# ESP32-DevKitC_EDA.net
KiCad netlist of a schematic drawn in EasyEDA Pro
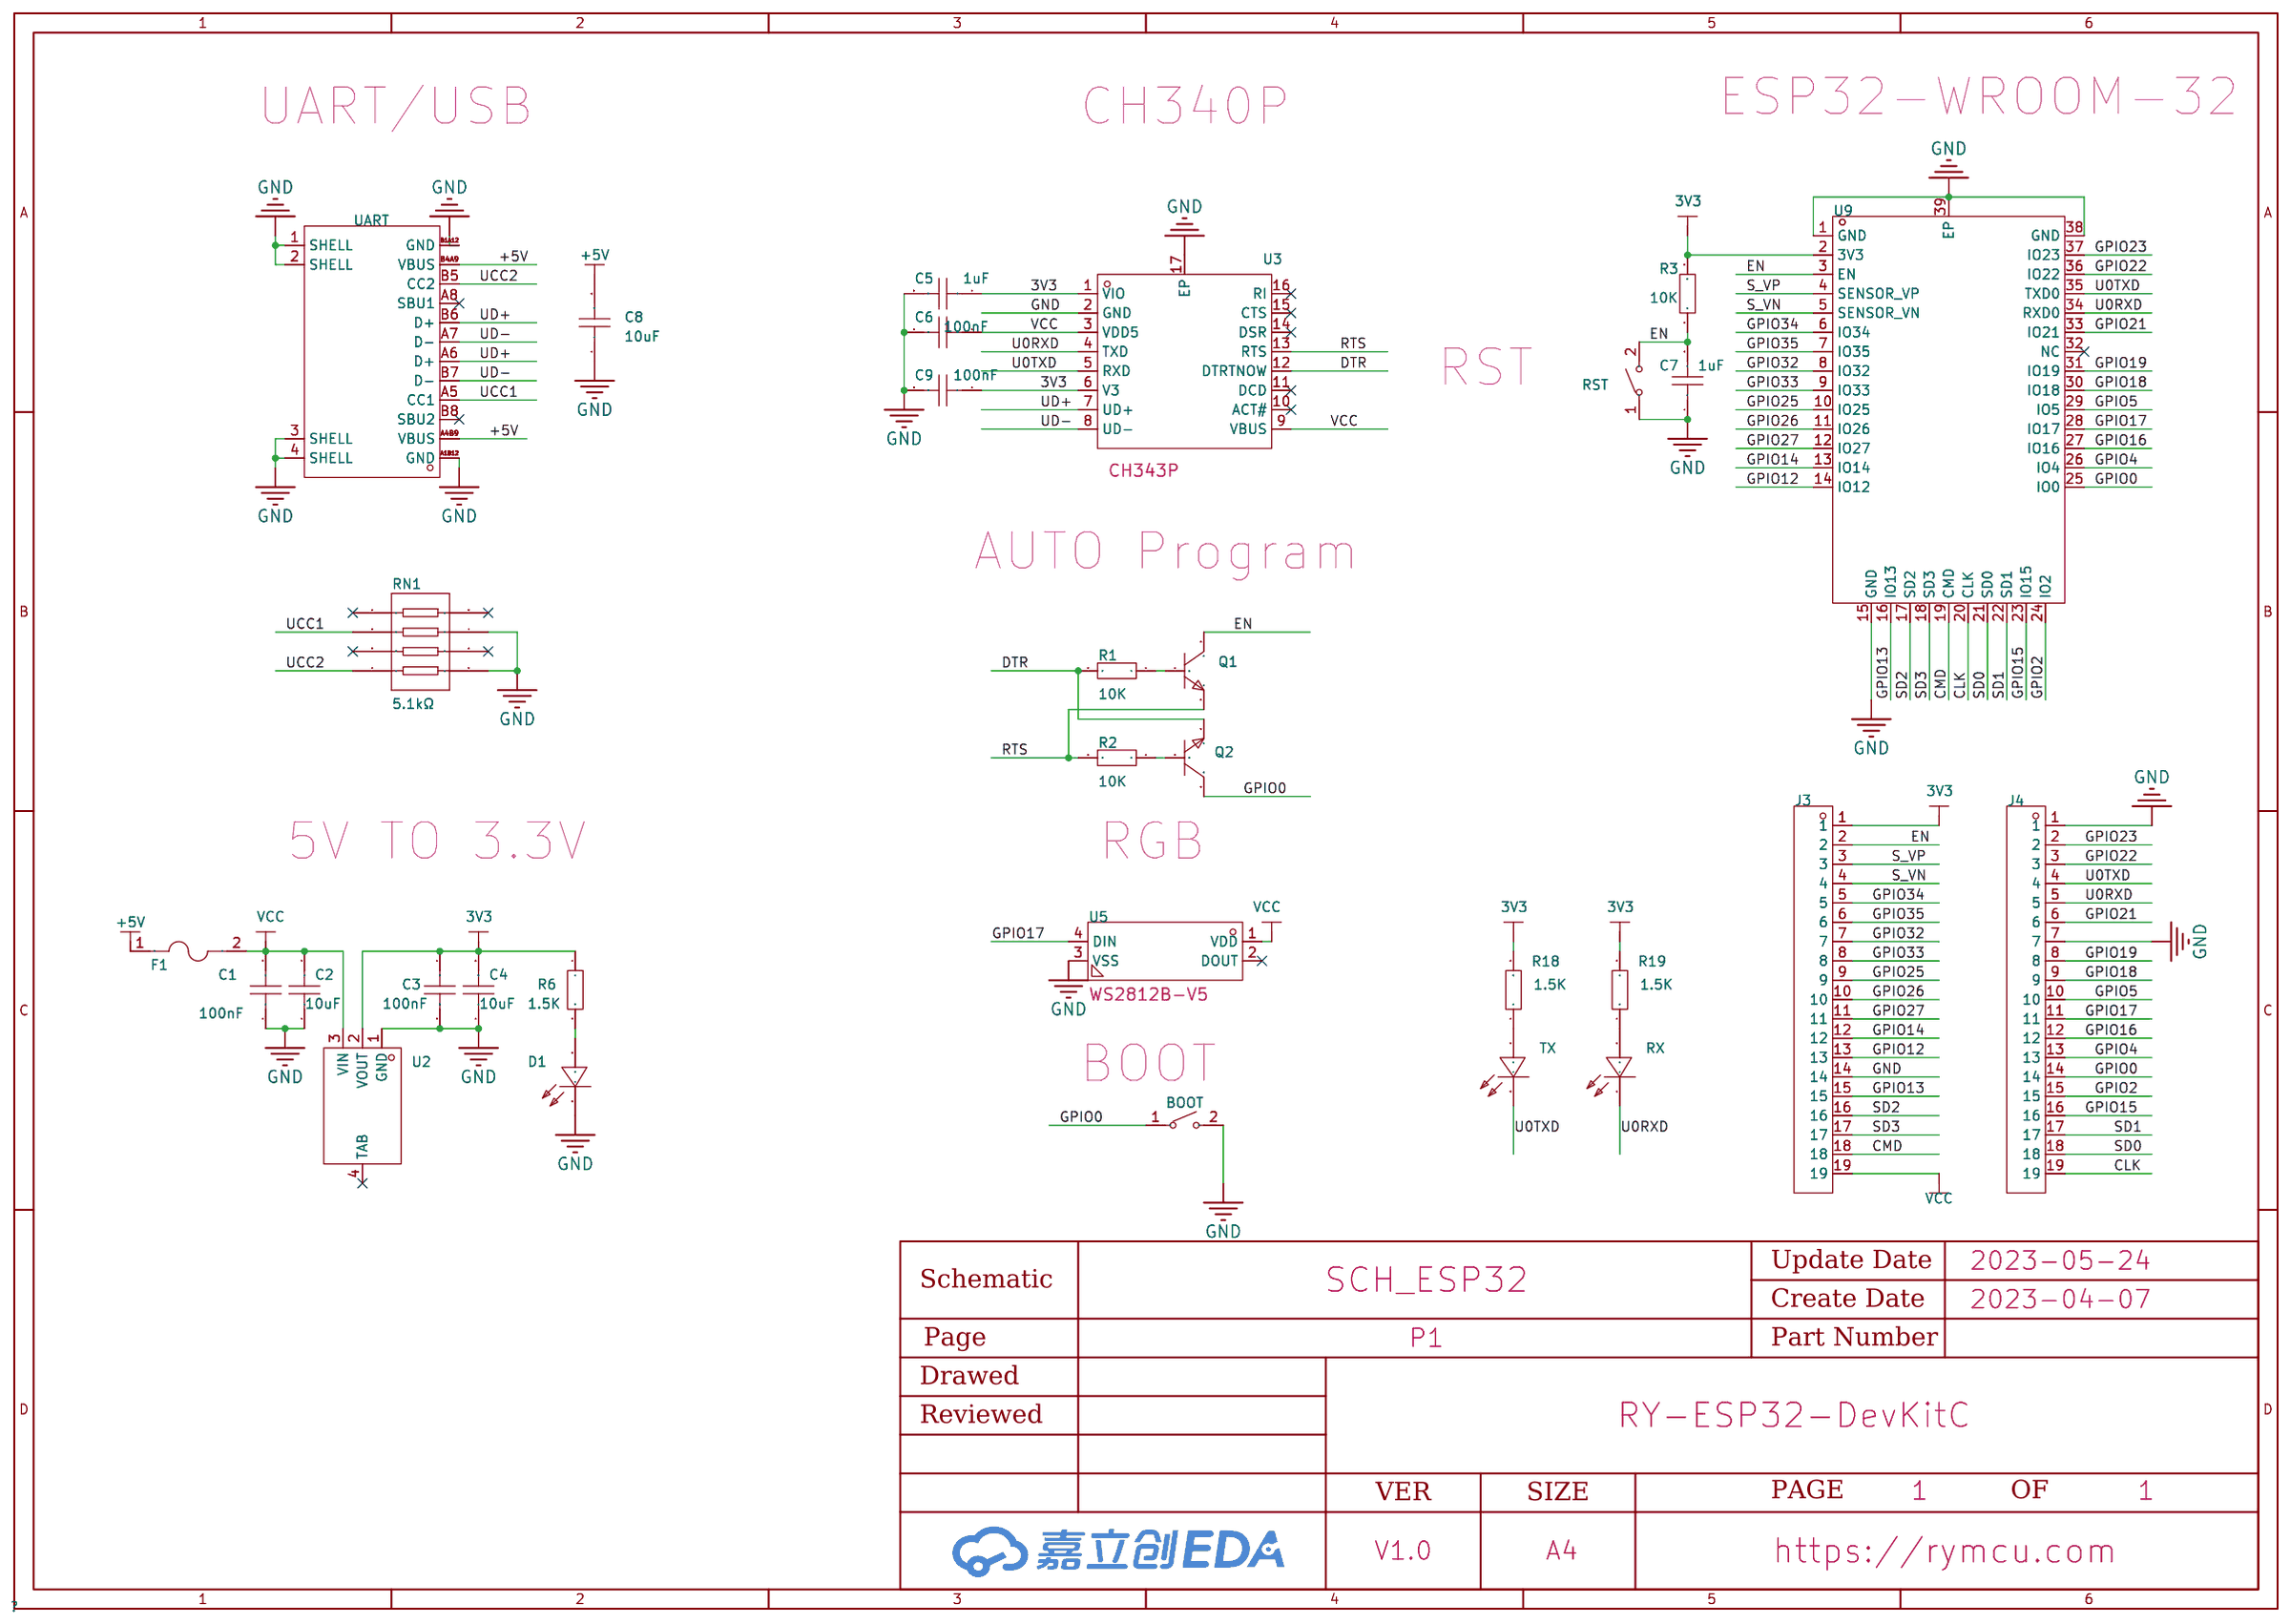
[diagram p0: schematic sheet]

(export (version "E")
  (design (tool "Eeschema 10.0.6"))
  (components
    (comp (ref "BOOT")
      (value "TS-1088R-02526")
      (footprint "easyedapro:SW-SMD_L3.9-W3.0-P4.45")
      (description "触点电流:50mA;额定电压(DC):12V;电路结构:单刀单掷;安装方式:立贴;按钮形状:圆形按钮;带灯:-;开关长度:3.9mm;开关宽度:2.93mm;开关高度:2.5mm;")
      (fields (field (name "Manufacturer") "XUNPU(讯普)"))
      (libsource (lib "easyedapro") (part "TS-1088R-02526"))
    )
    (comp (ref "C1")
      (value "100nF")
      (fields
        (field (name "Manufacturer Part") "CC0603KRX7R9BB104")
        (field (name "Manufacturer") "YAGEO(国巨)")
      )
      (libsource (lib "easyedapro") (part "CC0603KRX7R9BB104"))
    )
    (comp (ref "C2")
      (value "10uF")
      (fields
        (field (name "Manufacturer Part") "CC0805FRNPO9BN330")
        (field (name "Manufacturer") "YAGEO(国巨)")
      )
      (libsource (lib "easyedapro") (part "CC0805FRNPO9BN330"))
    )
    (comp (ref "C3")
      (value "100nF")
      (fields
        (field (name "Manufacturer Part") "CC0603KRX7R9BB104")
        (field (name "Manufacturer") "YAGEO(国巨)")
      )
      (libsource (lib "easyedapro") (part "CC0603KRX7R9BB104"))
    )
    (comp (ref "C4")
      (value "10uF")
      (fields
        (field (name "Manufacturer Part") "CC0805FRNPO9BN330")
        (field (name "Manufacturer") "YAGEO(国巨)")
      )
      (libsource (lib "easyedapro") (part "CC0805FRNPO9BN330"))
    )
    (comp (ref "C5")
      (value "1uF")
      (fields
        (field (name "Manufacturer Part") "CC0603KRX7R9BB104")
        (field (name "Manufacturer") "YAGEO(国巨)")
      )
      (libsource (lib "easyedapro") (part "CC0603KRX7R9BB104"))
    )
    (comp (ref "C6")
      (value "100nF")
      (fields
        (field (name "Manufacturer Part") "CC0603KRX7R9BB104")
        (field (name "Manufacturer") "YAGEO(国巨)")
      )
      (libsource (lib "easyedapro") (part "CC0603KRX7R9BB104"))
    )
    (comp (ref "C7")
      (value "1uF")
      (fields
        (field (name "Manufacturer Part") "CC0603KRX7R9BB104")
        (field (name "Manufacturer") "YAGEO(国巨)")
      )
      (libsource (lib "easyedapro") (part "CC0603KRX7R9BB104"))
    )
    (comp (ref "C8")
      (value "10uF")
      (fields
        (field (name "Manufacturer Part") "CC0805FRNPO9BN330")
        (field (name "Manufacturer") "YAGEO(国巨)")
      )
      (libsource (lib "easyedapro") (part "CC0805FRNPO9BN330"))
    )
    (comp (ref "C9")
      (value "100nF")
      (fields
        (field (name "Manufacturer Part") "CC0603KRX7R9BB104")
        (field (name "Manufacturer") "YAGEO(国巨)")
      )
      (libsource (lib "easyedapro") (part "CC0603KRX7R9BB104"))
    )
    (comp (ref "D1")
      (value "NCD0603R3")
      (fields (field (name "Manufacturer") "国星光电"))
      (libsource (lib "easyedapro") (part "NCD0603R3"))
    )
    (comp (ref "F1")
      (value "~")
      (footprint "easyedapro:F0805")
      (fields (field (name "Manufacturer Part") "ASMD0805-075") (field (name "Manufacturer") "JDTfuse集电通"))
      (libsource (lib "easyedapro") (part "ASMD0805-075"))
    )
    (comp (ref "J3")
      (value "2.54-1*19P反弯针")
      (footprint "easyedapro:HDR-TH_19P-P2.54-H-M-W10.5")
      (fields (field (name "Manufacturer") "BOOMELE(博穆精密)"))
      (libsource (lib "easyedapro") (part "DIP19"))
    )
    (comp (ref "J4")
      (value "2.54-1*19P反弯针")
      (footprint "easyedapro:HDR-TH_19P-P2.54-H-M-W10.5")
      (fields (field (name "Manufacturer") "BOOMELE(博穆精密)"))
      (libsource (lib "easyedapro") (part "DIP19"))
    )
    (comp (ref "Q1")
      (value "L8050QLT1G")
      (footprint "easyedapro:SOT-23-3_L2.9-W1.3-P1.90-LS2.4-BR")
      (description "集电极电流(Ic):800mA;集射极击穿电压(Vceo):25V;功率(Pd):225mW;晶体管类型:NPN;")
      (fields (field (name "Manufacturer") "LRC(乐山无线电)"))
      (libsource (lib "easyedapro") (part "L8050QLT1G"))
    )
    (comp (ref "Q2")
      (value "L8050QLT1G")
      (footprint "easyedapro:SOT-23-3_L2.9-W1.3-P1.90-LS2.4-BR")
      (description "集电极电流(Ic):800mA;集射极击穿电压(Vceo):25V;功率(Pd):225mW;晶体管类型:NPN;")
      (fields (field (name "Manufacturer") "LRC(乐山无线电)"))
      (libsource (lib "easyedapro") (part "L8050QLT1G"))
    )
    (comp (ref "R1")
      (value "10K")
      (footprint "easyedapro:R0603")
      (description "电阻类型:薄膜电阻;阻值:10kΩ;精度:±0.1%;功率:100mW;温度系数:±25ppm/;最大工作电压:75V;工作温度范围:-55~+155;")
      (fields
        (field (name "Manufacturer Part") "TR0603B10K0P0525Z")
        (field (name "Manufacturer") "EVER OHMS(天二科技)")
      )
      (libsource (lib "easyedapro") (part "TR0603B10KP05250.1W"))
    )
    (comp (ref "R2")
      (value "10K")
      (footprint "easyedapro:R0603")
      (description "电阻类型:薄膜电阻;阻值:10kΩ;精度:±0.1%;功率:100mW;温度系数:±25ppm/;最大工作电压:75V;工作温度范围:-55~+155;")
      (fields
        (field (name "Manufacturer Part") "TR0603B10K0P0525Z")
        (field (name "Manufacturer") "EVER OHMS(天二科技)")
      )
      (libsource (lib "easyedapro") (part "TR0603B10KP05250.1W"))
    )
    (comp (ref "R3")
      (value "10K")
      (footprint "easyedapro:R0603")
      (description "电阻类型:薄膜电阻;阻值:10kΩ;精度:±0.1%;功率:100mW;温度系数:±25ppm/;最大工作电压:75V;工作温度范围:-55~+155;")
      (fields
        (field (name "Manufacturer Part") "TR0603B10K0P0525Z")
        (field (name "Manufacturer") "EVER OHMS(天二科技)")
      )
      (libsource (lib "easyedapro") (part "TR0603B10KP05250.1W"))
    )
    (comp (ref "R6")
      (value "1.5K")
      (footprint "easyedapro:R0603")
      (description "电阻类型:薄膜电阻;阻值:10kΩ;精度:±0.1%;功率:100mW;温度系数:±25ppm/;最大工作电压:75V;工作温度范围:-55~+155;")
      (fields
        (field (name "Manufacturer Part") "TR0603B10K0P0525Z")
        (field (name "Manufacturer") "EVER OHMS(天二科技)")
      )
      (libsource (lib "easyedapro") (part "TR0603B10KP05250.1W"))
    )
    (comp (ref "R18")
      (value "1.5K")
      (footprint "easyedapro:R0603")
      (description "电阻类型:薄膜电阻;阻值:10kΩ;精度:±0.1%;功率:100mW;温度系数:±25ppm/;最大工作电压:75V;工作温度范围:-55~+155;")
      (fields
        (field (name "Manufacturer Part") "TR0603B10K0P0525Z")
        (field (name "Manufacturer") "EVER OHMS(天二科技)")
      )
      (libsource (lib "easyedapro") (part "TR0603B10KP05250.1W"))
    )
    (comp (ref "R19")
      (value "1.5K")
      (footprint "easyedapro:R0603")
      (description "电阻类型:薄膜电阻;阻值:10kΩ;精度:±0.1%;功率:100mW;温度系数:±25ppm/;最大工作电压:75V;工作温度范围:-55~+155;")
      (fields
        (field (name "Manufacturer Part") "TR0603B10K0P0525Z")
        (field (name "Manufacturer") "EVER OHMS(天二科技)")
      )
      (libsource (lib "easyedapro") (part "TR0603B10KP05250.1W"))
    )
    (comp (ref "RN1")
      (value "5.1kΩ")
      (footprint "easyedapro:RES-ARRAY-SMD_0603-8P-L3.2-W1.6-BL")
      (description "阻值:5.1kΩ;精度:±5%;单个元件功率:62.5mW;温度系数:±200ppm/;电阻器数:4;引脚数:8;")
      (fields
        (field (name "Manufacturer Part") "4D03WGJ0512T5E")
        (field (name "Manufacturer") "UNI-ROYAL(厚声)")
      )
      (libsource (lib "easyedapro") (part "4D03WGJ0512T5E"))
    )
    (comp (ref "RST")
      (value "TS-1088R-02526")
      (footprint "easyedapro:SW-SMD_L3.9-W3.0-P4.45")
      (description "触点电流:50mA;额定电压(DC):12V;电路结构:单刀单掷;安装方式:立贴;按钮形状:圆形按钮;带灯:-;开关长度:3.9mm;开关宽度:2.93mm;开关高度:2.5mm;")
      (fields (field (name "Manufacturer") "XUNPU(讯普)"))
      (libsource (lib "easyedapro") (part "TS-1088R-02526"))
    )
    (comp (ref "RX")
      (value "NCD0603R3")
      (footprint "easyedapro:LED0603-R-RD_RED")
      (description "尺寸1.6x0.8x0.8；IF=20ma：1.6~2.6v，620~640nm,51~150mcd金线，光强高，功耗低，可靠性好，寿命长")
      (fields (field (name "Manufacturer") "国星光电"))
      (libsource (lib "easyedapro") (part "NCD0603R3"))
    )
    (comp (ref "TX")
      (value "NCD0603R3")
      (fields (field (name "Manufacturer") "国星光电"))
      (libsource (lib "easyedapro") (part "NCD0603R3"))
    )
    (comp (ref "U2")
      (value "~")
      (footprint "easyedapro:SOT-223-3_L6.5-W3.4-P2.30-LS7.0-BR")
      (description "输出类型:固定;输出极性:正;输出通道数:1;最大输入电压:18V;输出电压:3.3V;压差:1.4V@(1A);输出电流:800mA;电源纹波抑制比(PRSS):-;")
      (fields (field (name "Manufacturer Part") "AMS1117-3.3") (field (name "Manufacturer") "PUOLOP(迪浦)"))
      (libsource (lib "easyedapro") (part "AMS1117-3.3_C351784"))
    )
    (comp (ref "U3")
      (value "CH343P")
      (footprint "easyedapro:TQFN-16_L3.0-W3.0-P0.50-BL-EP1.7")
      (description "类型:-;协议类别:-;驱动器/接收器数:-;数据速率:-;")
      (fields (field (name "Manufacturer") "WCH(南京沁恒)") (field (name "LCSC Part Name") "CH343P"))
      (libsource (lib "easyedapro") (part "CH343P"))
    )
    (comp (ref "U5")
      (value "WS2812B-V5")
      (footprint "easyedapro:LED-SMD_4P-L5.0-W5.0-TL_WS2812B-B")
      (fields (field (name "LCSC Part Name") "WS2812B-V5"))
      (libsource (lib "easyedapro") (part "WS2812B-V5"))
    )
    (comp (ref "U9")
      (value "ESP32-WROOM-32")
      (footprint "easyedapro:WIFIM-SMD_ESP-WROOM-32")
      (description "WiFi+双模蓝牙 双核CPU 网口 顶配MCU 低功耗蓝牙 ESP32系列ESP-WROOM-32模组/ESP-32S 4MB")
      (fields (field (name "Manufacturer") "ESPRESSIF(乐鑫)"))
      (libsource (lib "easyedapro") (part "ESP-WROOM-32"))
    )
    (comp (ref "UART")
      (value "~")
      (footprint "easyedapro:USB-C-SMD_G-SWITCH_GT-USB-7010EN")
      (description "连接器类型:Type-C;公母:母座;触点数量:16;端口数量:1;安装方式:卧贴;")
      (fields
        (field (name "Manufacturer Part") "HC-TYPE-C-16P-01A-R")
        (field (name "Manufacturer") "HCTL(华灿天禄)")
      )
      (libsource (lib "easyedapro") (part "HC-TYPE-C-16P-01A-R"))
    )
  )
  (nets
    (net (code "1") (name "+5V") (class "Default")
      (node (ref "C8") (pin "2") (pinfunction "2_2") (pintype "input"))
      (node (ref "F1") (pin "1") (pinfunction "1_1") (pintype "input"))
      (node (ref "UART") (pin "A4B9") (pinfunction "VBUS_A4B9") (pintype "input"))
      (node (ref "UART") (pin "B4A9") (pinfunction "VBUS_B4A9") (pintype "input"))
    )
    (net (code "2") (name "/CLK") (class "Default")
      (node (ref "J4") (pin "19") (pinfunction "19_19") (pintype "input"))
      (node (ref "U9") (pin "20") (pinfunction "CLK_20") (pintype "input"))
    )
    (net (code "3") (name "/CMD") (class "Default")
      (node (ref "J3") (pin "18") (pinfunction "18_18") (pintype "input"))
      (node (ref "U9") (pin "19") (pinfunction "CMD_19") (pintype "input"))
    )
    (net (code "4") (name "/DTR") (class "Default")
      (node (ref "Q2") (pin "2") (pinfunction "E_2") (pintype "input"))
      (node (ref "R1") (pin "2") (pinfunction "2_2") (pintype "input"))
      (node (ref "U3") (pin "12") (pinfunction "DTRTNOW_12") (pintype "input"))
    )
    (net (code "5") (name "/EN") (class "Default")
      (node (ref "C7") (pin "2") (pinfunction "2_2") (pintype "input"))
      (node (ref "J3") (pin "2") (pinfunction "2_2") (pintype "input"))
      (node (ref "Q1") (pin "3") (pinfunction "C_3") (pintype "input"))
      (node (ref "R3") (pin "1") (pinfunction "1_1") (pintype "input"))
      (node (ref "RST") (pin "2") (pinfunction "2_2") (pintype "input"))
      (node (ref "U9") (pin "3") (pinfunction "EN_3") (pintype "input"))
    )
    (net (code "6") (name "/GPIO0") (class "Default")
      (node (ref "BOOT") (pin "1") (pinfunction "1_1") (pintype "input"))
      (node (ref "J4") (pin "14") (pinfunction "14_14") (pintype "input"))
      (node (ref "Q2") (pin "3") (pinfunction "C_3") (pintype "input"))
      (node (ref "U9") (pin "25") (pinfunction "IO0_25") (pintype "input"))
    )
    (net (code "7") (name "/GPIO2") (class "Default")
      (node (ref "J4") (pin "15") (pinfunction "15_15") (pintype "input"))
      (node (ref "U9") (pin "24") (pinfunction "IO2_24") (pintype "input"))
    )
    (net (code "8") (name "/GPIO4") (class "Default")
      (node (ref "J4") (pin "13") (pinfunction "13_13") (pintype "input"))
      (node (ref "U9") (pin "26") (pinfunction "IO4_26") (pintype "input"))
    )
    (net (code "9") (name "/GPIO5") (class "Default")
      (node (ref "J4") (pin "10") (pinfunction "10_10") (pintype "input"))
      (node (ref "U9") (pin "29") (pinfunction "IO5_29") (pintype "input"))
    )
    (net (code "10") (name "/GPIO12") (class "Default")
      (node (ref "J3") (pin "13") (pinfunction "13_13") (pintype "input"))
      (node (ref "U9") (pin "14") (pinfunction "IO12_14") (pintype "input"))
    )
    (net (code "11") (name "/GPIO13") (class "Default")
      (node (ref "J3") (pin "15") (pinfunction "15_15") (pintype "input"))
      (node (ref "U9") (pin "16") (pinfunction "IO13_16") (pintype "input"))
    )
    (net (code "12") (name "/GPIO14") (class "Default")
      (node (ref "J3") (pin "12") (pinfunction "12_12") (pintype "input"))
      (node (ref "U9") (pin "13") (pinfunction "IO14_13") (pintype "input"))
    )
    (net (code "13") (name "/GPIO15") (class "Default")
      (node (ref "J4") (pin "16") (pinfunction "16_16") (pintype "input"))
      (node (ref "U9") (pin "23") (pinfunction "IO15_23") (pintype "input"))
    )
    (net (code "14") (name "/GPIO16") (class "Default")
      (node (ref "J4") (pin "12") (pinfunction "12_12") (pintype "input"))
      (node (ref "U9") (pin "27") (pinfunction "IO16_27") (pintype "input"))
    )
    (net (code "15") (name "/GPIO17") (class "Default")
      (node (ref "J4") (pin "11") (pinfunction "11_11") (pintype "input"))
      (node (ref "U5") (pin "4") (pinfunction "DIN_4") (pintype "input"))
      (node (ref "U9") (pin "28") (pinfunction "IO17_28") (pintype "input"))
    )
    (net (code "16") (name "/GPIO18") (class "Default")
      (node (ref "J4") (pin "9") (pinfunction "9_9") (pintype "input"))
      (node (ref "U9") (pin "30") (pinfunction "IO18_30") (pintype "input"))
    )
    (net (code "17") (name "/GPIO19") (class "Default")
      (node (ref "J4") (pin "8") (pinfunction "8_8") (pintype "input"))
      (node (ref "U9") (pin "31") (pinfunction "IO19_31") (pintype "input"))
    )
    (net (code "18") (name "/GPIO21") (class "Default")
      (node (ref "J4") (pin "6") (pinfunction "6_6") (pintype "input"))
      (node (ref "U9") (pin "33") (pinfunction "IO21_33") (pintype "input"))
    )
    (net (code "19") (name "/GPIO22") (class "Default")
      (node (ref "J4") (pin "3") (pinfunction "3_3") (pintype "input"))
      (node (ref "U9") (pin "36") (pinfunction "IO22_36") (pintype "input"))
    )
    (net (code "20") (name "/GPIO23") (class "Default")
      (node (ref "J4") (pin "2") (pinfunction "2_2") (pintype "input"))
      (node (ref "U9") (pin "37") (pinfunction "IO23_37") (pintype "input"))
    )
    (net (code "21") (name "/GPIO25") (class "Default")
      (node (ref "J3") (pin "9") (pinfunction "9_9") (pintype "input"))
      (node (ref "U9") (pin "10") (pinfunction "IO25_10") (pintype "input"))
    )
    (net (code "22") (name "/GPIO26") (class "Default")
      (node (ref "J3") (pin "10") (pinfunction "10_10") (pintype "input"))
      (node (ref "U9") (pin "11") (pinfunction "IO26_11") (pintype "input"))
    )
    (net (code "23") (name "/GPIO27") (class "Default")
      (node (ref "J3") (pin "11") (pinfunction "11_11") (pintype "input"))
      (node (ref "U9") (pin "12") (pinfunction "IO27_12") (pintype "input"))
    )
    (net (code "24") (name "/GPIO32") (class "Default")
      (node (ref "J3") (pin "7") (pinfunction "7_7") (pintype "input"))
      (node (ref "U9") (pin "8") (pinfunction "IO32_8") (pintype "input"))
    )
    (net (code "25") (name "/GPIO33") (class "Default")
      (node (ref "J3") (pin "8") (pinfunction "8_8") (pintype "input"))
      (node (ref "U9") (pin "9") (pinfunction "IO33_9") (pintype "input"))
    )
    (net (code "26") (name "/GPIO34") (class "Default")
      (node (ref "J3") (pin "5") (pinfunction "5_5") (pintype "input"))
      (node (ref "U9") (pin "6") (pinfunction "IO34_6") (pintype "input"))
    )
    (net (code "27") (name "/GPIO35") (class "Default")
      (node (ref "J3") (pin "6") (pinfunction "6_6") (pintype "input"))
      (node (ref "U9") (pin "7") (pinfunction "IO35_7") (pintype "input"))
    )
    (net (code "28") (name "/RTS") (class "Default")
      (node (ref "Q1") (pin "2") (pinfunction "E_2") (pintype "input"))
      (node (ref "R2") (pin "2") (pinfunction "2_2") (pintype "input"))
      (node (ref "U3") (pin "13") (pinfunction "RTS_13") (pintype "input"))
    )
    (net (code "29") (name "/SD0") (class "Default")
      (node (ref "J4") (pin "18") (pinfunction "18_18") (pintype "input"))
      (node (ref "U9") (pin "21") (pinfunction "SD0_21") (pintype "input"))
    )
    (net (code "30") (name "/SD1") (class "Default")
      (node (ref "J4") (pin "17") (pinfunction "17_17") (pintype "input"))
      (node (ref "U9") (pin "22") (pinfunction "SD1_22") (pintype "input"))
    )
    (net (code "31") (name "/SD2") (class "Default")
      (node (ref "J3") (pin "16") (pinfunction "16_16") (pintype "input"))
      (node (ref "U9") (pin "17") (pinfunction "SD2_17") (pintype "input"))
    )
    (net (code "32") (name "/SD3") (class "Default")
      (node (ref "J3") (pin "17") (pinfunction "17_17") (pintype "input"))
      (node (ref "U9") (pin "18") (pinfunction "SD3_18") (pintype "input"))
    )
    (net (code "33") (name "/S_VN") (class "Default")
      (node (ref "J3") (pin "4") (pinfunction "4_4") (pintype "input"))
      (node (ref "U9") (pin "5") (pinfunction "SENSOR_VN_5") (pintype "input"))
    )
    (net (code "34") (name "/S_VP") (class "Default")
      (node (ref "J3") (pin "3") (pinfunction "3_3") (pintype "input"))
      (node (ref "U9") (pin "4") (pinfunction "SENSOR_VP_4") (pintype "input"))
    )
    (net (code "35") (name "/U0RXD") (class "Default")
      (node (ref "J4") (pin "5") (pinfunction "5_5") (pintype "input"))
      (node (ref "RX") (pin "2") (pinfunction "K_2") (pintype "input"))
      (node (ref "U3") (pin "4") (pinfunction "TXD_4") (pintype "input"))
      (node (ref "U9") (pin "34") (pinfunction "RXD0_34") (pintype "input"))
    )
    (net (code "36") (name "/U0TXD") (class "Default")
      (node (ref "J4") (pin "4") (pinfunction "4_4") (pintype "input"))
      (node (ref "TX") (pin "2") (pinfunction "K_2") (pintype "input"))
      (node (ref "U3") (pin "5") (pinfunction "RXD_5") (pintype "input"))
      (node (ref "U9") (pin "35") (pinfunction "TXD0_35") (pintype "input"))
    )
    (net (code "37") (name "/UCC1") (class "Default")
      (node (ref "RN1") (pin "2") (pinfunction "2_2") (pintype "input"))
      (node (ref "UART") (pin "A5") (pinfunction "CC1_A5") (pintype "input"))
    )
    (net (code "38") (name "/UCC2") (class "Default")
      (node (ref "RN1") (pin "4") (pinfunction "4_4") (pintype "input"))
      (node (ref "UART") (pin "B5") (pinfunction "CC2_B5") (pintype "input"))
    )
    (net (code "39") (name "/UD+") (class "Default")
      (node (ref "U3") (pin "7") (pinfunction "UD+_7") (pintype "input"))
      (node (ref "UART") (pin "A6") (pinfunction "D+_A6") (pintype "input"))
      (node (ref "UART") (pin "B6") (pinfunction "D+_B6") (pintype "input"))
    )
    (net (code "40") (name "/UD-") (class "Default")
      (node (ref "U3") (pin "8") (pinfunction "UD-_8") (pintype "input"))
      (node (ref "UART") (pin "A7") (pinfunction "D-_A7") (pintype "input"))
      (node (ref "UART") (pin "B7") (pinfunction "D-_B7") (pintype "input"))
    )
    (net (code "41") (name "3V3") (class "Default")
      (node (ref "C3") (pin "1") (pinfunction "1_1") (pintype "input"))
      (node (ref "C4") (pin "2") (pinfunction "2_2") (pintype "input"))
      (node (ref "C5") (pin "1") (pinfunction "1_1") (pintype "input"))
      (node (ref "C9") (pin "1") (pinfunction "1_1") (pintype "input"))
      (node (ref "J3") (pin "1") (pinfunction "1_1") (pintype "input"))
      (node (ref "R18") (pin "2") (pinfunction "2_2") (pintype "input"))
      (node (ref "R19") (pin "2") (pinfunction "2_2") (pintype "input"))
      (node (ref "R3") (pin "2") (pinfunction "2_2") (pintype "input"))
      (node (ref "R6") (pin "1") (pinfunction "1_1") (pintype "input"))
      (node (ref "U2") (pin "2") (pinfunction "VOUT_2") (pintype "input"))
      (node (ref "U3") (pin "1") (pinfunction "VIO_1") (pintype "input"))
      (node (ref "U3") (pin "6") (pinfunction "V3_6") (pintype "input"))
      (node (ref "U9") (pin "2") (pinfunction "3V3_2") (pintype "input"))
    )
    (net (code "42") (name "GND") (class "Default")
      (node (ref "BOOT") (pin "2") (pinfunction "2_2") (pintype "input"))
      (node (ref "C1") (pin "1") (pinfunction "1_1") (pintype "input"))
      (node (ref "C2") (pin "1") (pinfunction "1_1") (pintype "input"))
      (node (ref "C3") (pin "2") (pinfunction "2_2") (pintype "input"))
      (node (ref "C4") (pin "1") (pinfunction "1_1") (pintype "input"))
      (node (ref "C5") (pin "2") (pinfunction "2_2") (pintype "input"))
      (node (ref "C6") (pin "2") (pinfunction "2_2") (pintype "input"))
      (node (ref "C7") (pin "1") (pinfunction "1_1") (pintype "input"))
      (node (ref "C8") (pin "1") (pinfunction "1_1") (pintype "input"))
      (node (ref "C9") (pin "2") (pinfunction "2_2") (pintype "input"))
      (node (ref "D1") (pin "2") (pinfunction "K_2") (pintype "input"))
      (node (ref "J3") (pin "14") (pinfunction "14_14") (pintype "input"))
      (node (ref "J4") (pin "1") (pinfunction "1_1") (pintype "input"))
      (node (ref "J4") (pin "7") (pinfunction "7_7") (pintype "input"))
      (node (ref "RN1") (pin "5") (pinfunction "5_5") (pintype "input"))
      (node (ref "RN1") (pin "7") (pinfunction "7_7") (pintype "input"))
      (node (ref "RST") (pin "1") (pinfunction "1_1") (pintype "input"))
      (node (ref "U2") (pin "1") (pinfunction "GND_1") (pintype "input"))
      (node (ref "U3") (pin "17") (pinfunction "EP_17") (pintype "input"))
      (node (ref "U3") (pin "2") (pinfunction "GND_2") (pintype "input"))
      (node (ref "U5") (pin "3") (pinfunction "VSS_3") (pintype "input"))
      (node (ref "U9") (pin "1") (pinfunction "GND_1") (pintype "input"))
      (node (ref "U9") (pin "15") (pinfunction "GND_15") (pintype "input"))
      (node (ref "U9") (pin "38") (pinfunction "GND_38") (pintype "input"))
      (node (ref "U9") (pin "39") (pinfunction "EP_39") (pintype "input"))
      (node (ref "UART") (pin "1") (pinfunction "SHELL_1") (pintype "input"))
      (node (ref "UART") (pin "2") (pinfunction "SHELL_2") (pintype "input"))
      (node (ref "UART") (pin "3") (pinfunction "SHELL_3") (pintype "input"))
      (node (ref "UART") (pin "4") (pinfunction "SHELL_4") (pintype "input"))
      (node (ref "UART") (pin "A1B12") (pinfunction "GND_A1B12") (pintype "input"))
      (node (ref "UART") (pin "B1A12") (pinfunction "GND_B1A12") (pintype "input"))
    )
    (net (code "43") (name "Net-(D1-A)") (class "Default")
      (node (ref "D1") (pin "1") (pinfunction "A_1") (pintype "input"))
      (node (ref "R6") (pin "2") (pinfunction "2_2") (pintype "input"))
    )
    (net (code "44") (name "Net-(Q1-B)") (class "Default")
      (node (ref "Q1") (pin "1") (pinfunction "B_1") (pintype "input"))
      (node (ref "R1") (pin "1") (pinfunction "1_1") (pintype "input"))
    )
    (net (code "45") (name "Net-(Q2-B)") (class "Default")
      (node (ref "Q2") (pin "1") (pinfunction "B_1") (pintype "input"))
      (node (ref "R2") (pin "1") (pinfunction "1_1") (pintype "input"))
    )
    (net (code "46") (name "Net-(RX-A)") (class "Default")
      (node (ref "R19") (pin "1") (pinfunction "1_1") (pintype "input"))
      (node (ref "RX") (pin "1") (pinfunction "A_1") (pintype "input"))
    )
    (net (code "47") (name "Net-(TX-A)") (class "Default")
      (node (ref "R18") (pin "1") (pinfunction "1_1") (pintype "input"))
      (node (ref "TX") (pin "1") (pinfunction "A_1") (pintype "input"))
    )
    (net (code "48") (name "VCC") (class "Default")
      (node (ref "C1") (pin "2") (pinfunction "2_2") (pintype "input"))
      (node (ref "C2") (pin "2") (pinfunction "2_2") (pintype "input"))
      (node (ref "C6") (pin "1") (pinfunction "1_1") (pintype "input"))
      (node (ref "F1") (pin "2") (pinfunction "2_2") (pintype "input"))
      (node (ref "J3") (pin "19") (pinfunction "19_19") (pintype "input"))
      (node (ref "U2") (pin "3") (pinfunction "VIN_3") (pintype "input"))
      (node (ref "U3") (pin "3") (pinfunction "VDD5_3") (pintype "input"))
      (node (ref "U3") (pin "9") (pinfunction "VBUS_9") (pintype "input"))
      (node (ref "U5") (pin "1") (pinfunction "VDD_1") (pintype "input"))
    )
    (net (code "49") (name "unconnected-(RN1-Pad1)") (class "Default")
      (node (ref "RN1") (pin "1") (pinfunction "1_1") (pintype "input+no_connect"))
    )
    (net (code "50") (name "unconnected-(RN1-Pad3)") (class "Default")
      (node (ref "RN1") (pin "3") (pinfunction "3_3") (pintype "input+no_connect"))
    )
    (net (code "51") (name "unconnected-(RN1-Pad6)") (class "Default")
      (node (ref "RN1") (pin "6") (pinfunction "6_6") (pintype "input+no_connect"))
    )
    (net (code "52") (name "unconnected-(RN1-Pad8)") (class "Default")
      (node (ref "RN1") (pin "8") (pinfunction "8_8") (pintype "input+no_connect"))
    )
    (net (code "53") (name "unconnected-(U2-TAB-Pad4)") (class "Default")
      (node (ref "U2") (pin "4") (pinfunction "TAB_4") (pintype "input+no_connect"))
    )
    (net (code "54") (name "unconnected-(U3-ACT#-Pad10)") (class "Default")
      (node (ref "U3") (pin "10") (pinfunction "ACT#_10") (pintype "input+no_connect"))
    )
    (net (code "55") (name "unconnected-(U3-CTS-Pad15)") (class "Default")
      (node (ref "U3") (pin "15") (pinfunction "CTS_15") (pintype "input+no_connect"))
    )
    (net (code "56") (name "unconnected-(U3-DCD-Pad11)") (class "Default")
      (node (ref "U3") (pin "11") (pinfunction "DCD_11") (pintype "input+no_connect"))
    )
    (net (code "57") (name "unconnected-(U3-DSR-Pad14)") (class "Default")
      (node (ref "U3") (pin "14") (pinfunction "DSR_14") (pintype "input+no_connect"))
    )
    (net (code "58") (name "unconnected-(U3-RI-Pad16)") (class "Default")
      (node (ref "U3") (pin "16") (pinfunction "RI_16") (pintype "input+no_connect"))
    )
    (net (code "59") (name "unconnected-(U5-DOUT-Pad2)") (class "Default")
      (node (ref "U5") (pin "2") (pinfunction "DOUT_2") (pintype "input+no_connect"))
    )
    (net (code "60") (name "unconnected-(U9-NC-Pad32)") (class "Default")
      (node (ref "U9") (pin "32") (pinfunction "NC_32") (pintype "input+no_connect"))
    )
    (net (code "61") (name "unconnected-(UART-SBU1-PadA8)") (class "Default")
      (node (ref "UART") (pin "A8") (pinfunction "SBU1_A8") (pintype "input+no_connect"))
    )
    (net (code "62") (name "unconnected-(UART-SBU2-PadB8)") (class "Default")
      (node (ref "UART") (pin "B8") (pinfunction "SBU2_B8") (pintype "input+no_connect"))
    )
  )
)
